# salsa_II_v3a.net
KiCad netlist of a schematic drawn in EAGLE
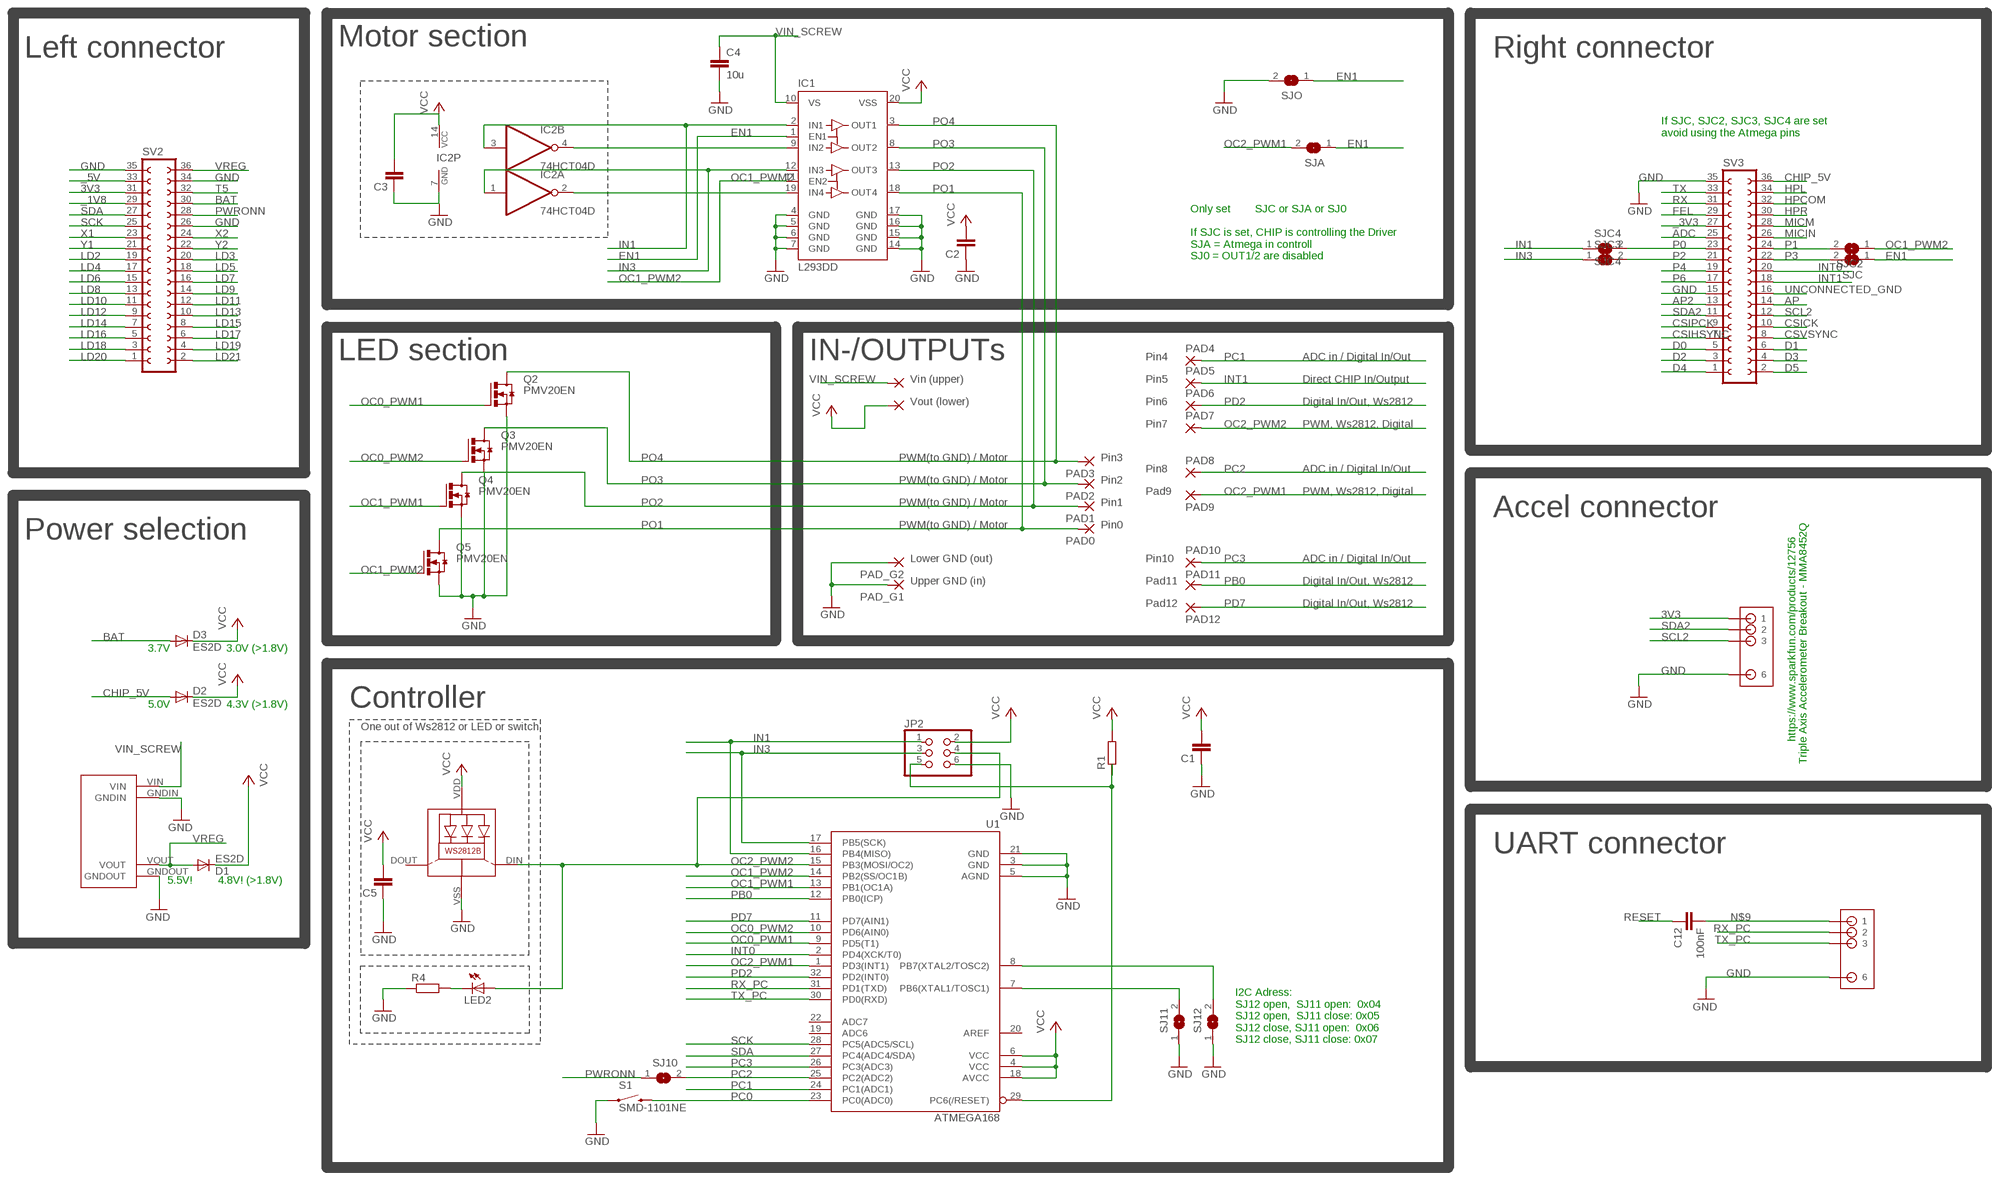
[diagram p0: schematic, sheet 1]

(export (version "E")
  (design (tool "Eeschema 10.0.6"))
  (components
    (comp (ref "C1")
      (value "C-EUC0805")
      (footprint "eagle-import:C0805")
      (libsource (lib "eagle-import") (part "C-EUC0805"))
    )
    (comp (ref "C2")
      (value "C-EUC0805")
      (footprint "eagle-import:C0805")
      (libsource (lib "eagle-import") (part "C-EUC0805"))
    )
    (comp (ref "C3")
      (value "C-EUC0805")
      (footprint "eagle-import:C0805")
      (libsource (lib "eagle-import") (part "C-EUC0805"))
    )
    (comp (ref "C4")
      (value "10u")
      (footprint "eagle-import:C1210")
      (libsource (lib "eagle-import") (part "C-EUC1210"))
    )
    (comp (ref "C5")
      (value "C-EUC0805")
      (footprint "eagle-import:C0805")
      (libsource (lib "eagle-import") (part "C-EUC0805"))
    )
    (comp (ref "C12")
      (value "100nF")
      (footprint "eagle-import:C1206")
      (libsource (lib "eagle-import") (part "C-EUC1206"))
    )
    (comp (ref "D1")
      (value "ES2D")
      (footprint "eagle-import:SMB")
      (libsource (lib "eagle-import") (part "ES2D"))
    )
    (comp (ref "D2")
      (value "ES2D")
      (footprint "eagle-import:SMB")
      (libsource (lib "eagle-import") (part "ES2D"))
    )
    (comp (ref "D3")
      (value "ES2D")
      (footprint "eagle-import:SMB")
      (libsource (lib "eagle-import") (part "ES2D"))
    )
    (comp (ref "IC1")
      (value "L293DD")
      (footprint "eagle-import:SO20")
      (libsource (lib "eagle-import") (part "L293DD"))
    )
    (comp (ref "IC2")
      (value "74HCT04D")
      (footprint "eagle-import:SO14")
      (libsource (lib "eagle-import") (part "7404DHCT"))
    )
    (comp (ref "JP2")
      (value "PINHD-2X3")
      (footprint "eagle-import:2X03")
      (libsource (lib "eagle-import") (part "PINHD-2X3"))
    )
    (comp (ref "LED1")
      (value "WS2812B")
      (footprint "eagle-import:WS2812B")
      (libsource (lib "eagle-import") (part "WS2812B"))
    )
    (comp (ref "LED2")
      (value "LEDCHIP-LED0805")
      (footprint "eagle-import:CHIP-LED0805")
      (libsource (lib "eagle-import") (part "LEDCHIP-LED0805"))
    )
    (comp (ref "PAD0")
      (value "3,17/1,3")
      (footprint "eagle-import:3,17_1,3")
      (libsource (lib "eagle-import") (part "3,17/1,3"))
    )
    (comp (ref "PAD1")
      (value "3,17/1,3")
      (footprint "eagle-import:3,17_1,3")
      (libsource (lib "eagle-import") (part "3,17/1,3"))
    )
    (comp (ref "PAD2")
      (value "3,17/1,3")
      (footprint "eagle-import:3,17_1,3")
      (libsource (lib "eagle-import") (part "3,17/1,3"))
    )
    (comp (ref "PAD3")
      (value "3,17/1,3")
      (footprint "eagle-import:3,17_1,3")
      (libsource (lib "eagle-import") (part "3,17/1,3"))
    )
    (comp (ref "PAD4")
      (value "3,17/1,3")
      (footprint "eagle-import:3,17_1,3")
      (libsource (lib "eagle-import") (part "3,17/1,3"))
    )
    (comp (ref "PAD5")
      (value "3,17/1,3")
      (footprint "eagle-import:3,17_1,3")
      (libsource (lib "eagle-import") (part "3,17/1,3"))
    )
    (comp (ref "PAD6")
      (value "3,17/1,3")
      (footprint "eagle-import:3,17_1,3")
      (libsource (lib "eagle-import") (part "3,17/1,3"))
    )
    (comp (ref "PAD7")
      (value "3,17/1,3")
      (footprint "eagle-import:3,17_1,3")
      (libsource (lib "eagle-import") (part "3,17/1,3"))
    )
    (comp (ref "PAD8")
      (value "3,17/1,3")
      (footprint "eagle-import:3,17_1,3")
      (libsource (lib "eagle-import") (part "3,17/1,3"))
    )
    (comp (ref "PAD9")
      (value "SMD2")
      (footprint "eagle-import:SMD1,27-2,54")
      (libsource (lib "eagle-import") (part "SMD2"))
    )
    (comp (ref "PAD10")
      (value "3,17/1,3")
      (footprint "eagle-import:3,17_1,3")
      (libsource (lib "eagle-import") (part "3,17/1,3"))
    )
    (comp (ref "PAD11")
      (value "WIREPADSMD1,27-254")
      (footprint "eagle-import:SMD1,27-2,54")
      (libsource (lib "eagle-import") (part "WIREPADSMD1,27-254"))
    )
    (comp (ref "PAD12")
      (value "SMD2")
      (footprint "eagle-import:SMD1,27-2,54")
      (libsource (lib "eagle-import") (part "SMD2"))
    )
    (comp (ref "PAD17")
      (value "3,17/1,3")
      (footprint "eagle-import:3,17_1,3")
      (libsource (lib "eagle-import") (part "3,17/1,3"))
    )
    (comp (ref "PAD_G1")
      (value "3,17/1,3")
      (footprint "eagle-import:3,17_1,3")
      (libsource (lib "eagle-import") (part "3,17/1,3"))
    )
    (comp (ref "PAD_G2")
      (value "3,17/1,3")
      (footprint "eagle-import:3,17_1,3")
      (libsource (lib "eagle-import") (part "3,17/1,3"))
    )
    (comp (ref "PAD_VIN")
      (value "3,17/1,3")
      (footprint "eagle-import:3,17_1,3")
      (libsource (lib "eagle-import") (part "3,17/1,3"))
    )
    (comp (ref "Q2")
      (value "PMV20EN")
      (footprint "eagle-import:SOT223")
      (libsource (lib "eagle-import") (part "NMOSFET_SMD_223"))
    )
    (comp (ref "Q3")
      (value "PMV20EN")
      (footprint "eagle-import:SOT223")
      (libsource (lib "eagle-import") (part "NMOSFET_SMD_223"))
    )
    (comp (ref "Q4")
      (value "PMV20EN")
      (footprint "eagle-import:SOT223")
      (libsource (lib "eagle-import") (part "NMOSFET_SMD_223"))
    )
    (comp (ref "Q5")
      (value "PMV20EN")
      (footprint "eagle-import:SOT223")
      (libsource (lib "eagle-import") (part "NMOSFET_SMD_223"))
    )
    (comp (ref "R1")
      (value "R-EU_M1206")
      (footprint "eagle-import:M1206")
      (libsource (lib "eagle-import") (part "R-EU_M1206"))
    )
    (comp (ref "R4")
      (value "R-EU_M1206")
      (footprint "eagle-import:M1206")
      (libsource (lib "eagle-import") (part "R-EU_M1206"))
    )
    (comp (ref "S1")
      (value "SMD-1101NE")
      (footprint "eagle-import:TACTILE-SWITCH-1101NE")
      (libsource (lib "eagle-import") (part "SWITCH-MOMENTARY-2-SMD-1101NE"))
    )
    (comp (ref "SJ10")
      (value "SJ")
      (footprint "eagle-import:SJ")
      (libsource (lib "eagle-import") (part "SJ"))
    )
    (comp (ref "SJ11")
      (value "SJ")
      (footprint "eagle-import:SJ")
      (libsource (lib "eagle-import") (part "SJ"))
    )
    (comp (ref "SJ12")
      (value "SJ")
      (footprint "eagle-import:SJ")
      (libsource (lib "eagle-import") (part "SJ"))
    )
    (comp (ref "SJA") (value "SJ") (footprint "eagle-import:SJ") (libsource (lib "eagle-import") (part "SJ")))
    (comp (ref "SJC") (value "SJ") (footprint "eagle-import:SJ") (libsource (lib "eagle-import") (part "SJ")))
    (comp (ref "SJC2")
      (value "SJ")
      (footprint "eagle-import:SJ")
      (libsource (lib "eagle-import") (part "SJ"))
    )
    (comp (ref "SJC3")
      (value "SJ")
      (footprint "eagle-import:SJ")
      (libsource (lib "eagle-import") (part "SJ"))
    )
    (comp (ref "SJC4")
      (value "SJC4")
      (footprint "eagle-import:SJ")
      (libsource (lib "eagle-import") (part "SJ"))
    )
    (comp (ref "SJO") (value "SJ") (footprint "eagle-import:SJ") (libsource (lib "eagle-import") (part "SJ")))
    (comp (ref "SV2")
      (value "FE18-2")
      (footprint "eagle-import:FE18-2")
      (libsource (lib "eagle-import") (part "FE18-2"))
    )
    (comp (ref "SV3")
      (value "FE18-2")
      (footprint "eagle-import:FE18-2")
      (libsource (lib "eagle-import") (part "FE18-2"))
    )
    (comp (ref "U$1")
      (value "MP1584EN")
      (footprint "eagle-import:MP1584EN")
      (libsource (lib "eagle-import") (part "MP1584EN"))
    )
    (comp (ref "U$3")
      (value "6_TO_4_HEADER")
      (footprint "eagle-import:6_TO_4_HEADER")
      (libsource (lib "eagle-import") (part "6_TO_4_HEADER"))
    )
    (comp (ref "U$4")
      (value "6_TO_4_HEADER")
      (footprint "eagle-import:6_TO_4_HEADER")
      (libsource (lib "eagle-import") (part "6_TO_4_HEADER"))
    )
    (comp (ref "U1")
      (value "ATMEGA168")
      (footprint "eagle-import:TQFP32-08")
      (libsource (lib "eagle-import") (part "ATMEGA168"))
    )
  )
  (nets
    (net (code "1") (name "/3V3") (class "Default")
      (node (ref "SV2") (pin "31") (pinfunction "31_31") (pintype "passive"))
      (node (ref "U$4") (pin "1") (pinfunction "1_1") (pintype "bidirectional"))
    )
    (net (code "2") (name "/ADC") (class "Default")
      (node (ref "SV3") (pin "25") (pinfunction "25_25") (pintype "passive"))
    )
    (net (code "3") (name "/AP") (class "Default")
      (node (ref "SV3") (pin "14") (pinfunction "14_14") (pintype "passive"))
    )
    (net (code "4") (name "/AP2") (class "Default")
      (node (ref "SV3") (pin "13") (pinfunction "13_13") (pintype "passive"))
    )
    (net (code "5") (name "/BAT") (class "Default")
      (node (ref "D3") (pin "A") (pinfunction "A_A") (pintype "passive"))
      (node (ref "SV2") (pin "30") (pinfunction "30_30") (pintype "passive"))
    )
    (net (code "6") (name "/CHIP_5V") (class "Default")
      (node (ref "D2") (pin "A") (pinfunction "A_A") (pintype "passive"))
      (node (ref "SV3") (pin "36") (pinfunction "36_36") (pintype "passive"))
    )
    (net (code "7") (name "/CSICK") (class "Default")
      (node (ref "SV3") (pin "10") (pinfunction "10_10") (pintype "passive"))
    )
    (net (code "8") (name "/CSIHSYNC") (class "Default")
      (node (ref "SV3") (pin "7") (pinfunction "7_7") (pintype "passive"))
    )
    (net (code "9") (name "/CSIPCK") (class "Default")
      (node (ref "SV3") (pin "9") (pinfunction "9_9") (pintype "passive"))
    )
    (net (code "10") (name "/CSVSYNC") (class "Default")
      (node (ref "SV3") (pin "8") (pinfunction "8_8") (pintype "passive"))
    )
    (net (code "11") (name "/D0") (class "Default")
      (node (ref "SV3") (pin "5") (pinfunction "5_5") (pintype "passive"))
    )
    (net (code "12") (name "/D1") (class "Default")
      (node (ref "SV3") (pin "6") (pinfunction "6_6") (pintype "passive"))
    )
    (net (code "13") (name "/D2") (class "Default")
      (node (ref "SV3") (pin "3") (pinfunction "3_3") (pintype "passive"))
    )
    (net (code "14") (name "/D3") (class "Default")
      (node (ref "SV3") (pin "4") (pinfunction "4_4") (pintype "passive"))
    )
    (net (code "15") (name "/D4") (class "Default")
      (node (ref "SV3") (pin "1") (pinfunction "1_1") (pintype "passive"))
    )
    (net (code "16") (name "/D5") (class "Default")
      (node (ref "SV3") (pin "2") (pinfunction "2_2") (pintype "passive"))
    )
    (net (code "17") (name "/EN1") (class "Default")
      (node (ref "IC1") (pin "1") (pinfunction "EN1_1") (pintype "input"))
      (node (ref "SJA") (pin "1") (pinfunction "1_1") (pintype "passive"))
      (node (ref "SJC") (pin "1") (pinfunction "1_1") (pintype "passive"))
      (node (ref "SJO") (pin "1") (pinfunction "1_1") (pintype "passive"))
    )
    (net (code "18") (name "/FEL") (class "Default")
      (node (ref "SV3") (pin "29") (pinfunction "29_29") (pintype "passive"))
    )
    (net (code "19") (name "/HPCOM") (class "Default")
      (node (ref "SV3") (pin "32") (pinfunction "32_32") (pintype "passive"))
    )
    (net (code "20") (name "/HPL") (class "Default")
      (node (ref "SV3") (pin "34") (pinfunction "34_34") (pintype "passive"))
    )
    (net (code "21") (name "/HPR") (class "Default")
      (node (ref "SV3") (pin "30") (pinfunction "30_30") (pintype "passive"))
    )
    (net (code "22") (name "/IN1") (class "Default")
      (node (ref "IC1") (pin "2") (pinfunction "IN1_2") (pintype "input"))
      (node (ref "IC2") (pin "3") (pinfunction "I_3") (pintype "input"))
      (node (ref "JP2") (pin "1") (pinfunction "1_1") (pintype "passive"))
      (node (ref "SJC4") (pin "1") (pinfunction "1_1") (pintype "passive"))
      (node (ref "U1") (pin "16") (pinfunction "PB4(MISO)_16") (pintype "bidirectional"))
    )
    (net (code "23") (name "/IN3") (class "Default")
      (node (ref "IC1") (pin "12") (pinfunction "IN3_12") (pintype "input"))
      (node (ref "IC2") (pin "1") (pinfunction "I_1") (pintype "input"))
      (node (ref "JP2") (pin "3") (pinfunction "3_3") (pintype "passive"))
      (node (ref "SJC3") (pin "1") (pinfunction "1_1") (pintype "passive"))
      (node (ref "U1") (pin "17") (pinfunction "PB5(SCK)_17") (pintype "bidirectional"))
    )
    (net (code "24") (name "/INT0") (class "Default")
      (node (ref "SV3") (pin "20") (pinfunction "20_20") (pintype "passive"))
      (node (ref "U1") (pin "2") (pinfunction "PD4(XCK/T0)_2") (pintype "bidirectional"))
    )
    (net (code "25") (name "/INT1") (class "Default")
      (node (ref "PAD5") (pin "1") (pinfunction "P_1") (pintype "passive"))
      (node (ref "SV3") (pin "18") (pinfunction "18_18") (pintype "passive"))
    )
    (net (code "26") (name "/LD2") (class "Default")
      (node (ref "SV2") (pin "19") (pinfunction "19_19") (pintype "passive"))
    )
    (net (code "27") (name "/LD3") (class "Default")
      (node (ref "SV2") (pin "20") (pinfunction "20_20") (pintype "passive"))
    )
    (net (code "28") (name "/LD4") (class "Default")
      (node (ref "SV2") (pin "17") (pinfunction "17_17") (pintype "passive"))
    )
    (net (code "29") (name "/LD5") (class "Default")
      (node (ref "SV2") (pin "18") (pinfunction "18_18") (pintype "passive"))
    )
    (net (code "30") (name "/LD6") (class "Default")
      (node (ref "SV2") (pin "15") (pinfunction "15_15") (pintype "passive"))
    )
    (net (code "31") (name "/LD7") (class "Default")
      (node (ref "SV2") (pin "16") (pinfunction "16_16") (pintype "passive"))
    )
    (net (code "32") (name "/LD8") (class "Default")
      (node (ref "SV2") (pin "13") (pinfunction "13_13") (pintype "passive"))
    )
    (net (code "33") (name "/LD9") (class "Default")
      (node (ref "SV2") (pin "14") (pinfunction "14_14") (pintype "passive"))
    )
    (net (code "34") (name "/LD10") (class "Default")
      (node (ref "SV2") (pin "11") (pinfunction "11_11") (pintype "passive"))
    )
    (net (code "35") (name "/LD11") (class "Default")
      (node (ref "SV2") (pin "12") (pinfunction "12_12") (pintype "passive"))
    )
    (net (code "36") (name "/LD12") (class "Default")
      (node (ref "SV2") (pin "9") (pinfunction "9_9") (pintype "passive"))
    )
    (net (code "37") (name "/LD13") (class "Default")
      (node (ref "SV2") (pin "10") (pinfunction "10_10") (pintype "passive"))
    )
    (net (code "38") (name "/LD14") (class "Default")
      (node (ref "SV2") (pin "7") (pinfunction "7_7") (pintype "passive"))
    )
    (net (code "39") (name "/LD15") (class "Default")
      (node (ref "SV2") (pin "8") (pinfunction "8_8") (pintype "passive"))
    )
    (net (code "40") (name "/LD16") (class "Default")
      (node (ref "SV2") (pin "5") (pinfunction "5_5") (pintype "passive"))
    )
    (net (code "41") (name "/LD17") (class "Default")
      (node (ref "SV2") (pin "6") (pinfunction "6_6") (pintype "passive"))
    )
    (net (code "42") (name "/LD18") (class "Default")
      (node (ref "SV2") (pin "3") (pinfunction "3_3") (pintype "passive"))
    )
    (net (code "43") (name "/LD19") (class "Default")
      (node (ref "SV2") (pin "4") (pinfunction "4_4") (pintype "passive"))
    )
    (net (code "44") (name "/LD20") (class "Default")
      (node (ref "SV2") (pin "1") (pinfunction "1_1") (pintype "passive"))
    )
    (net (code "45") (name "/LD21") (class "Default")
      (node (ref "SV2") (pin "2") (pinfunction "2_2") (pintype "passive"))
    )
    (net (code "46") (name "/MICIN") (class "Default")
      (node (ref "SV3") (pin "26") (pinfunction "26_26") (pintype "passive"))
    )
    (net (code "47") (name "/MICM") (class "Default")
      (node (ref "SV3") (pin "28") (pinfunction "28_28") (pintype "passive"))
    )
    (net (code "48") (name "/N$9") (class "Default")
      (node (ref "C12") (pin "2") (pinfunction "2_2") (pintype "passive"))
      (node (ref "U$3") (pin "1") (pinfunction "1_1") (pintype "bidirectional"))
    )
    (net (code "49") (name "/OC0_PWM1") (class "Default")
      (node (ref "Q2") (pin "1") (pinfunction "G_1") (pintype "passive"))
      (node (ref "U1") (pin "9") (pinfunction "PD5(T1)_9") (pintype "bidirectional"))
    )
    (net (code "50") (name "/OC0_PWM2") (class "Default")
      (node (ref "Q3") (pin "1") (pinfunction "G_1") (pintype "passive"))
      (node (ref "U1") (pin "10") (pinfunction "PD6(AIN0)_10") (pintype "bidirectional"))
    )
    (net (code "51") (name "/OC1_PWM1") (class "Default")
      (node (ref "Q4") (pin "1") (pinfunction "G_1") (pintype "passive"))
      (node (ref "U1") (pin "13") (pinfunction "PB1(OC1A)_13") (pintype "bidirectional"))
    )
    (net (code "52") (name "/OC1_PWM2") (class "Default")
      (node (ref "IC1") (pin "11") (pinfunction "EN2_11") (pintype "input"))
      (node (ref "Q5") (pin "1") (pinfunction "G_1") (pintype "passive"))
      (node (ref "SJC2") (pin "1") (pinfunction "1_1") (pintype "passive"))
      (node (ref "U1") (pin "14") (pinfunction "PB2(SS/OC1B)_14") (pintype "bidirectional"))
    )
    (net (code "53") (name "/OC2_PWM1") (class "Default")
      (node (ref "PAD9") (pin "1") (pinfunction "P_1") (pintype "passive"))
      (node (ref "SJA") (pin "2") (pinfunction "2_2") (pintype "passive"))
      (node (ref "U1") (pin "1") (pinfunction "PD3(INT1)_1") (pintype "bidirectional"))
    )
    (net (code "54") (name "/OC2_PWM2") (class "Default")
      (node (ref "JP2") (pin "4") (pinfunction "4_4") (pintype "passive"))
      (node (ref "LED1") (pin "DIN") (pinfunction "DI_DIN") (pintype "input"))
      (node (ref "LED2") (pin "A") (pinfunction "A_A") (pintype "passive"))
      (node (ref "PAD7") (pin "1") (pinfunction "P_1") (pintype "passive"))
      (node (ref "U1") (pin "15") (pinfunction "PB3(MOSI/OC2)_15") (pintype "bidirectional"))
    )
    (net (code "55") (name "/P0") (class "Default")
      (node (ref "SJC4") (pin "2") (pinfunction "2_2") (pintype "passive"))
      (node (ref "SV3") (pin "23") (pinfunction "23_23") (pintype "passive"))
    )
    (net (code "56") (name "/P1") (class "Default")
      (node (ref "SJC2") (pin "2") (pinfunction "2_2") (pintype "passive"))
      (node (ref "SV3") (pin "24") (pinfunction "24_24") (pintype "passive"))
    )
    (net (code "57") (name "/P2") (class "Default")
      (node (ref "SJC3") (pin "2") (pinfunction "2_2") (pintype "passive"))
      (node (ref "SV3") (pin "21") (pinfunction "21_21") (pintype "passive"))
    )
    (net (code "58") (name "/P3") (class "Default")
      (node (ref "SJC") (pin "2") (pinfunction "2_2") (pintype "passive"))
      (node (ref "SV3") (pin "22") (pinfunction "22_22") (pintype "passive"))
    )
    (net (code "59") (name "/P4") (class "Default")
      (node (ref "SV3") (pin "19") (pinfunction "19_19") (pintype "passive"))
    )
    (net (code "60") (name "/P6") (class "Default")
      (node (ref "SV3") (pin "17") (pinfunction "17_17") (pintype "passive"))
    )
    (net (code "61") (name "/PB0") (class "Default")
      (node (ref "PAD11") (pin "1") (pinfunction "P_1") (pintype "passive"))
      (node (ref "U1") (pin "12") (pinfunction "PB0(ICP)_12") (pintype "bidirectional"))
    )
    (net (code "62") (name "/PC0") (class "Default")
      (node (ref "S1") (pin "P$2") (pinfunction "2_P$2") (pintype "passive"))
      (node (ref "U1") (pin "23") (pinfunction "PC0(ADC0)_23") (pintype "bidirectional"))
    )
    (net (code "63") (name "/PC1") (class "Default")
      (node (ref "PAD4") (pin "1") (pinfunction "P_1") (pintype "passive"))
      (node (ref "U1") (pin "24") (pinfunction "PC1(ADC1)_24") (pintype "bidirectional"))
    )
    (net (code "64") (name "/PC2") (class "Default")
      (node (ref "PAD8") (pin "1") (pinfunction "P_1") (pintype "passive"))
      (node (ref "SJ10") (pin "2") (pinfunction "2_2") (pintype "passive"))
      (node (ref "U1") (pin "25") (pinfunction "PC2(ADC2)_25") (pintype "bidirectional"))
    )
    (net (code "65") (name "/PC3") (class "Default")
      (node (ref "PAD10") (pin "1") (pinfunction "P_1") (pintype "passive"))
      (node (ref "U1") (pin "26") (pinfunction "PC3(ADC3)_26") (pintype "bidirectional"))
    )
    (net (code "66") (name "/PD2") (class "Default")
      (node (ref "PAD6") (pin "1") (pinfunction "P_1") (pintype "passive"))
      (node (ref "U1") (pin "32") (pinfunction "PD2(INT0)_32") (pintype "bidirectional"))
    )
    (net (code "67") (name "/PD7") (class "Default")
      (node (ref "PAD12") (pin "1") (pinfunction "P_1") (pintype "passive"))
      (node (ref "U1") (pin "11") (pinfunction "PD7(AIN1)_11") (pintype "bidirectional"))
    )
    (net (code "68") (name "/PO1") (class "Default")
      (node (ref "IC1") (pin "18") (pinfunction "OUT4_18") (pintype "output"))
      (node (ref "PAD0") (pin "1") (pinfunction "P_1") (pintype "passive"))
      (node (ref "Q5") (pin "2") (pinfunction "D_2") (pintype "passive"))
      (node (ref "Q5") (pin "4") (pinfunction "D_4") (pintype "passive"))
    )
    (net (code "69") (name "/PO2") (class "Default")
      (node (ref "IC1") (pin "13") (pinfunction "OUT3_13") (pintype "output"))
      (node (ref "PAD1") (pin "1") (pinfunction "P_1") (pintype "passive"))
      (node (ref "Q4") (pin "2") (pinfunction "D_2") (pintype "passive"))
      (node (ref "Q4") (pin "4") (pinfunction "D_4") (pintype "passive"))
    )
    (net (code "70") (name "/PO3") (class "Default")
      (node (ref "IC1") (pin "8") (pinfunction "OUT2_8") (pintype "output"))
      (node (ref "PAD2") (pin "1") (pinfunction "P_1") (pintype "passive"))
      (node (ref "Q3") (pin "2") (pinfunction "D_2") (pintype "passive"))
      (node (ref "Q3") (pin "4") (pinfunction "D_4") (pintype "passive"))
    )
    (net (code "71") (name "/PO4") (class "Default")
      (node (ref "IC1") (pin "3") (pinfunction "OUT1_3") (pintype "output"))
      (node (ref "PAD3") (pin "1") (pinfunction "P_1") (pintype "passive"))
      (node (ref "Q2") (pin "2") (pinfunction "D_2") (pintype "passive"))
      (node (ref "Q2") (pin "4") (pinfunction "D_4") (pintype "passive"))
    )
    (net (code "72") (name "/PWRONN") (class "Default")
      (node (ref "SJ10") (pin "1") (pinfunction "1_1") (pintype "passive"))
      (node (ref "SV2") (pin "28") (pinfunction "28_28") (pintype "passive"))
    )
    (net (code "73") (name "/RESET") (class "Default")
      (node (ref "C12") (pin "1") (pinfunction "1_1") (pintype "passive"))
      (node (ref "JP2") (pin "5") (pinfunction "5_5") (pintype "passive"))
      (node (ref "R1") (pin "1") (pinfunction "1_1") (pintype "passive"))
      (node (ref "U1") (pin "29") (pinfunction "PC6(/RESET)_29") (pintype "bidirectional"))
    )
    (net (code "74") (name "/RX") (class "Default")
      (node (ref "SV3") (pin "31") (pinfunction "31_31") (pintype "passive"))
    )
    (net (code "75") (name "/RX_PC") (class "Default")
      (node (ref "U$3") (pin "2") (pinfunction "2_2") (pintype "bidirectional"))
      (node (ref "U1") (pin "31") (pinfunction "PD1(TXD)_31") (pintype "bidirectional"))
    )
    (net (code "76") (name "/SCK") (class "Default")
      (node (ref "SV2") (pin "25") (pinfunction "25_25") (pintype "passive"))
      (node (ref "U1") (pin "28") (pinfunction "PC5(ADC5/SCL)_28") (pintype "bidirectional"))
    )
    (net (code "77") (name "/SCL2") (class "Default")
      (node (ref "SV3") (pin "12") (pinfunction "12_12") (pintype "passive"))
      (node (ref "U$4") (pin "3") (pinfunction "3_3") (pintype "bidirectional"))
    )
    (net (code "78") (name "/SDA") (class "Default")
      (node (ref "SV2") (pin "27") (pinfunction "27_27") (pintype "passive"))
      (node (ref "U1") (pin "27") (pinfunction "PC4(ADC4/SDA)_27") (pintype "bidirectional"))
    )
    (net (code "79") (name "/SDA2") (class "Default")
      (node (ref "SV3") (pin "11") (pinfunction "11_11") (pintype "passive"))
      (node (ref "U$4") (pin "2") (pinfunction "2_2") (pintype "bidirectional"))
    )
    (net (code "80") (name "/T5") (class "Default")
      (node (ref "SV2") (pin "32") (pinfunction "32_32") (pintype "passive"))
    )
    (net (code "81") (name "/TX") (class "Default")
      (node (ref "SV3") (pin "33") (pinfunction "33_33") (pintype "passive"))
    )
    (net (code "82") (name "/TX_PC") (class "Default")
      (node (ref "U$3") (pin "3") (pinfunction "3_3") (pintype "bidirectional"))
      (node (ref "U1") (pin "30") (pinfunction "PD0(RXD)_30") (pintype "bidirectional"))
    )
    (net (code "83") (name "/UNCONNECTED_GND") (class "Default")
      (node (ref "SV3") (pin "16") (pinfunction "16_16") (pintype "passive"))
    )
    (net (code "84") (name "/VIN_SCREW") (class "Default")
      (node (ref "C4") (pin "1") (pinfunction "1_1") (pintype "passive"))
      (node (ref "IC1") (pin "10") (pinfunction "VS_10") (pintype "power_in"))
      (node (ref "PAD_VIN") (pin "1") (pinfunction "P_1") (pintype "passive"))
      (node (ref "U$1") (pin "VIN") (pinfunction "VIN_VIN") (pintype "power_in"))
    )
    (net (code "85") (name "/VREG") (class "Default")
      (node (ref "D1") (pin "A") (pinfunction "A_A") (pintype "passive"))
      (node (ref "SV2") (pin "36") (pinfunction "36_36") (pintype "passive"))
      (node (ref "U$1") (pin "VOUT") (pinfunction "VOUT_VOUT") (pintype "power_in"))
    )
    (net (code "86") (name "/X1") (class "Default")
      (node (ref "SV2") (pin "23") (pinfunction "23_23") (pintype "passive"))
    )
    (net (code "87") (name "/X2") (class "Default")
      (node (ref "SV2") (pin "24") (pinfunction "24_24") (pintype "passive"))
    )
    (net (code "88") (name "/Y1") (class "Default")
      (node (ref "SV2") (pin "21") (pinfunction "21_21") (pintype "passive"))
    )
    (net (code "89") (name "/Y2") (class "Default")
      (node (ref "SV2") (pin "22") (pinfunction "22_22") (pintype "passive"))
    )
    (net (code "90") (name "/_1V8") (class "Default")
      (node (ref "SV2") (pin "29") (pinfunction "29_29") (pintype "passive"))
    )
    (net (code "91") (name "/_3V3") (class "Default")
      (node (ref "SV3") (pin "27") (pinfunction "27_27") (pintype "passive"))
    )
    (net (code "92") (name "/_5V") (class "Default")
      (node (ref "SV2") (pin "33") (pinfunction "33_33") (pintype "passive"))
    )
    (net (code "93") (name "GND") (class "Default")
      (node (ref "C1") (pin "1") (pinfunction "1_1") (pintype "passive"))
      (node (ref "C2") (pin "1") (pinfunction "1_1") (pintype "passive"))
      (node (ref "C3") (pin "1") (pinfunction "1_1") (pintype "passive"))
      (node (ref "C4") (pin "2") (pinfunction "2_2") (pintype "passive"))
      (node (ref "C5") (pin "1") (pinfunction "1_1") (pintype "passive"))
      (node (ref "IC1") (pin "14") (pinfunction "GND_14") (pintype "power_in"))
      (node (ref "IC1") (pin "15") (pinfunction "GND_15") (pintype "power_in"))
      (node (ref "IC1") (pin "16") (pinfunction "GND_16") (pintype "power_in"))
      (node (ref "IC1") (pin "17") (pinfunction "GND_17") (pintype "power_in"))
      (node (ref "IC1") (pin "4") (pinfunction "GND_4") (pintype "power_in"))
      (node (ref "IC1") (pin "5") (pinfunction "GND_5") (pintype "power_in"))
      (node (ref "IC1") (pin "6") (pinfunction "GND_6") (pintype "power_in"))
      (node (ref "IC1") (pin "7") (pinfunction "GND_7") (pintype "power_in"))
      (node (ref "IC2") (pin "7") (pinfunction "GND_7") (pintype "power_in"))
      (node (ref "JP2") (pin "6") (pinfunction "6_6") (pintype "passive"))
      (node (ref "LED1") (pin "VSS") (pinfunction "GND_VSS") (pintype "power_in"))
      (node (ref "PAD_G1") (pin "1") (pinfunction "P_1") (pintype "passive"))
      (node (ref "PAD_G2") (pin "1") (pinfunction "P_1") (pintype "passive"))
      (node (ref "Q2") (pin "3") (pinfunction "S_3") (pintype "passive"))
      (node (ref "Q3") (pin "3") (pinfunction "S_3") (pintype "passive"))
      (node (ref "Q4") (pin "3") (pinfunction "S_3") (pintype "passive"))
      (node (ref "Q5") (pin "3") (pinfunction "S_3") (pintype "passive"))
      (node (ref "R4") (pin "1") (pinfunction "1_1") (pintype "passive"))
      (node (ref "S1") (pin "P$1") (pinfunction "1_P$1") (pintype "passive"))
      (node (ref "SJ11") (pin "1") (pinfunction "1_1") (pintype "passive"))
      (node (ref "SJ12") (pin "1") (pinfunction "1_1") (pintype "passive"))
      (node (ref "SJO") (pin "2") (pinfunction "2_2") (pintype "passive"))
      (node (ref "SV2") (pin "26") (pinfunction "26_26") (pintype "passive"))
      (node (ref "SV2") (pin "34") (pinfunction "34_34") (pintype "passive"))
      (node (ref "SV2") (pin "35") (pinfunction "35_35") (pintype "passive"))
      (node (ref "SV3") (pin "15") (pinfunction "15_15") (pintype "passive"))
      (node (ref "SV3") (pin "35") (pinfunction "35_35") (pintype "passive"))
      (node (ref "U$1") (pin "GNDIN") (pinfunction "GNDIN_GNDIN") (pintype "power_in"))
      (node (ref "U$1") (pin "GNDOUT") (pinfunction "GNDOUT_GNDOUT") (pintype "power_in"))
      (node (ref "U$3") (pin "6") (pinfunction "6_6") (pintype "bidirectional"))
      (node (ref "U$4") (pin "6") (pinfunction "6_6") (pintype "bidirectional"))
      (node (ref "U1") (pin "21") (pinfunction "GND_21") (pintype "bidirectional"))
      (node (ref "U1") (pin "3") (pinfunction "GND_3") (pintype "bidirectional"))
      (node (ref "U1") (pin "5") (pinfunction "AGND_5") (pintype "bidirectional"))
    )
    (net (code "94") (name "Net-(IC1-IN2)") (class "Default")
      (node (ref "IC1") (pin "9") (pinfunction "IN2_9") (pintype "input"))
      (node (ref "IC2") (pin "4") (pinfunction "O_4") (pintype "output"))
    )
    (net (code "95") (name "Net-(IC1-IN4)") (class "Default")
      (node (ref "IC1") (pin "19") (pinfunction "IN4_19") (pintype "input"))
      (node (ref "IC2") (pin "2") (pinfunction "O_2") (pintype "output"))
    )
    (net (code "96") (name "Net-(LED2-PadC)") (class "Default")
      (node (ref "LED2") (pin "C") (pinfunction "C_C") (pintype "passive"))
      (node (ref "R4") (pin "2") (pinfunction "2_2") (pintype "passive"))
    )
    (net (code "97") (name "Net-(U1-PB6(XTAL1{slash}TOSC1))") (class "Default")
      (node (ref "SJ11") (pin "2") (pinfunction "2_2") (pintype "passive"))
      (node (ref "U1") (pin "7") (pinfunction "PB6(XTAL1/TOSC1)_7") (pintype "bidirectional"))
    )
    (net (code "98") (name "Net-(U1-PB7(XTAL2{slash}TOSC2))") (class "Default")
      (node (ref "SJ12") (pin "2") (pinfunction "2_2") (pintype "passive"))
      (node (ref "U1") (pin "8") (pinfunction "PB7(XTAL2/TOSC2)_8") (pintype "bidirectional"))
    )
    (net (code "99") (name "VCC") (class "Default")
      (node (ref "C1") (pin "2") (pinfunction "2_2") (pintype "passive"))
      (node (ref "C2") (pin "2") (pinfunction "2_2") (pintype "passive"))
      (node (ref "C3") (pin "2") (pinfunction "2_2") (pintype "passive"))
      (node (ref "C5") (pin "2") (pinfunction "2_2") (pintype "passive"))
      (node (ref "D1") (pin "C") (pinfunction "C_C") (pintype "passive"))
      (node (ref "D2") (pin "C") (pinfunction "C_C") (pintype "passive"))
      (node (ref "D3") (pin "C") (pinfunction "C_C") (pintype "passive"))
      (node (ref "IC1") (pin "20") (pinfunction "VSS_20") (pintype "power_in"))
      (node (ref "IC2") (pin "14") (pinfunction "VCC_14") (pintype "power_in"))
      (node (ref "JP2") (pin "2") (pinfunction "2_2") (pintype "passive"))
      (node (ref "LED1") (pin "VDD") (pinfunction "VDD_VDD") (pintype "power_in"))
      (node (ref "PAD17") (pin "1") (pinfunction "P_1") (pintype "passive"))
      (node (ref "R1") (pin "2") (pinfunction "2_2") (pintype "passive"))
      (node (ref "U1") (pin "18") (pinfunction "AVCC_18") (pintype "bidirectional"))
      (node (ref "U1") (pin "4") (pinfunction "VCC_4") (pintype "bidirectional"))
      (node (ref "U1") (pin "6") (pinfunction "VCC_6") (pintype "bidirectional"))
    )
    (net (code "100") (name "unconnected-(LED1-DO-PadDOUT)") (class "Default")
      (node (ref "LED1") (pin "DOUT") (pinfunction "DO_DOUT") (pintype "output"))
    )
    (net (code "101") (name "unconnected-(U1-ADC6-Pad19)") (class "Default")
      (node (ref "U1") (pin "19") (pinfunction "ADC6_19") (pintype "bidirectional"))
    )
    (net (code "102") (name "unconnected-(U1-ADC7-Pad22)") (class "Default")
      (node (ref "U1") (pin "22") (pinfunction "ADC7_22") (pintype "bidirectional"))
    )
    (net (code "103") (name "unconnected-(U1-AREF-Pad20)") (class "Default")
      (node (ref "U1") (pin "20") (pinfunction "AREF_20") (pintype "bidirectional"))
    )
  )
)
